# Phototransistor.net
KiCad netlist of a schematic drawn in EAGLE
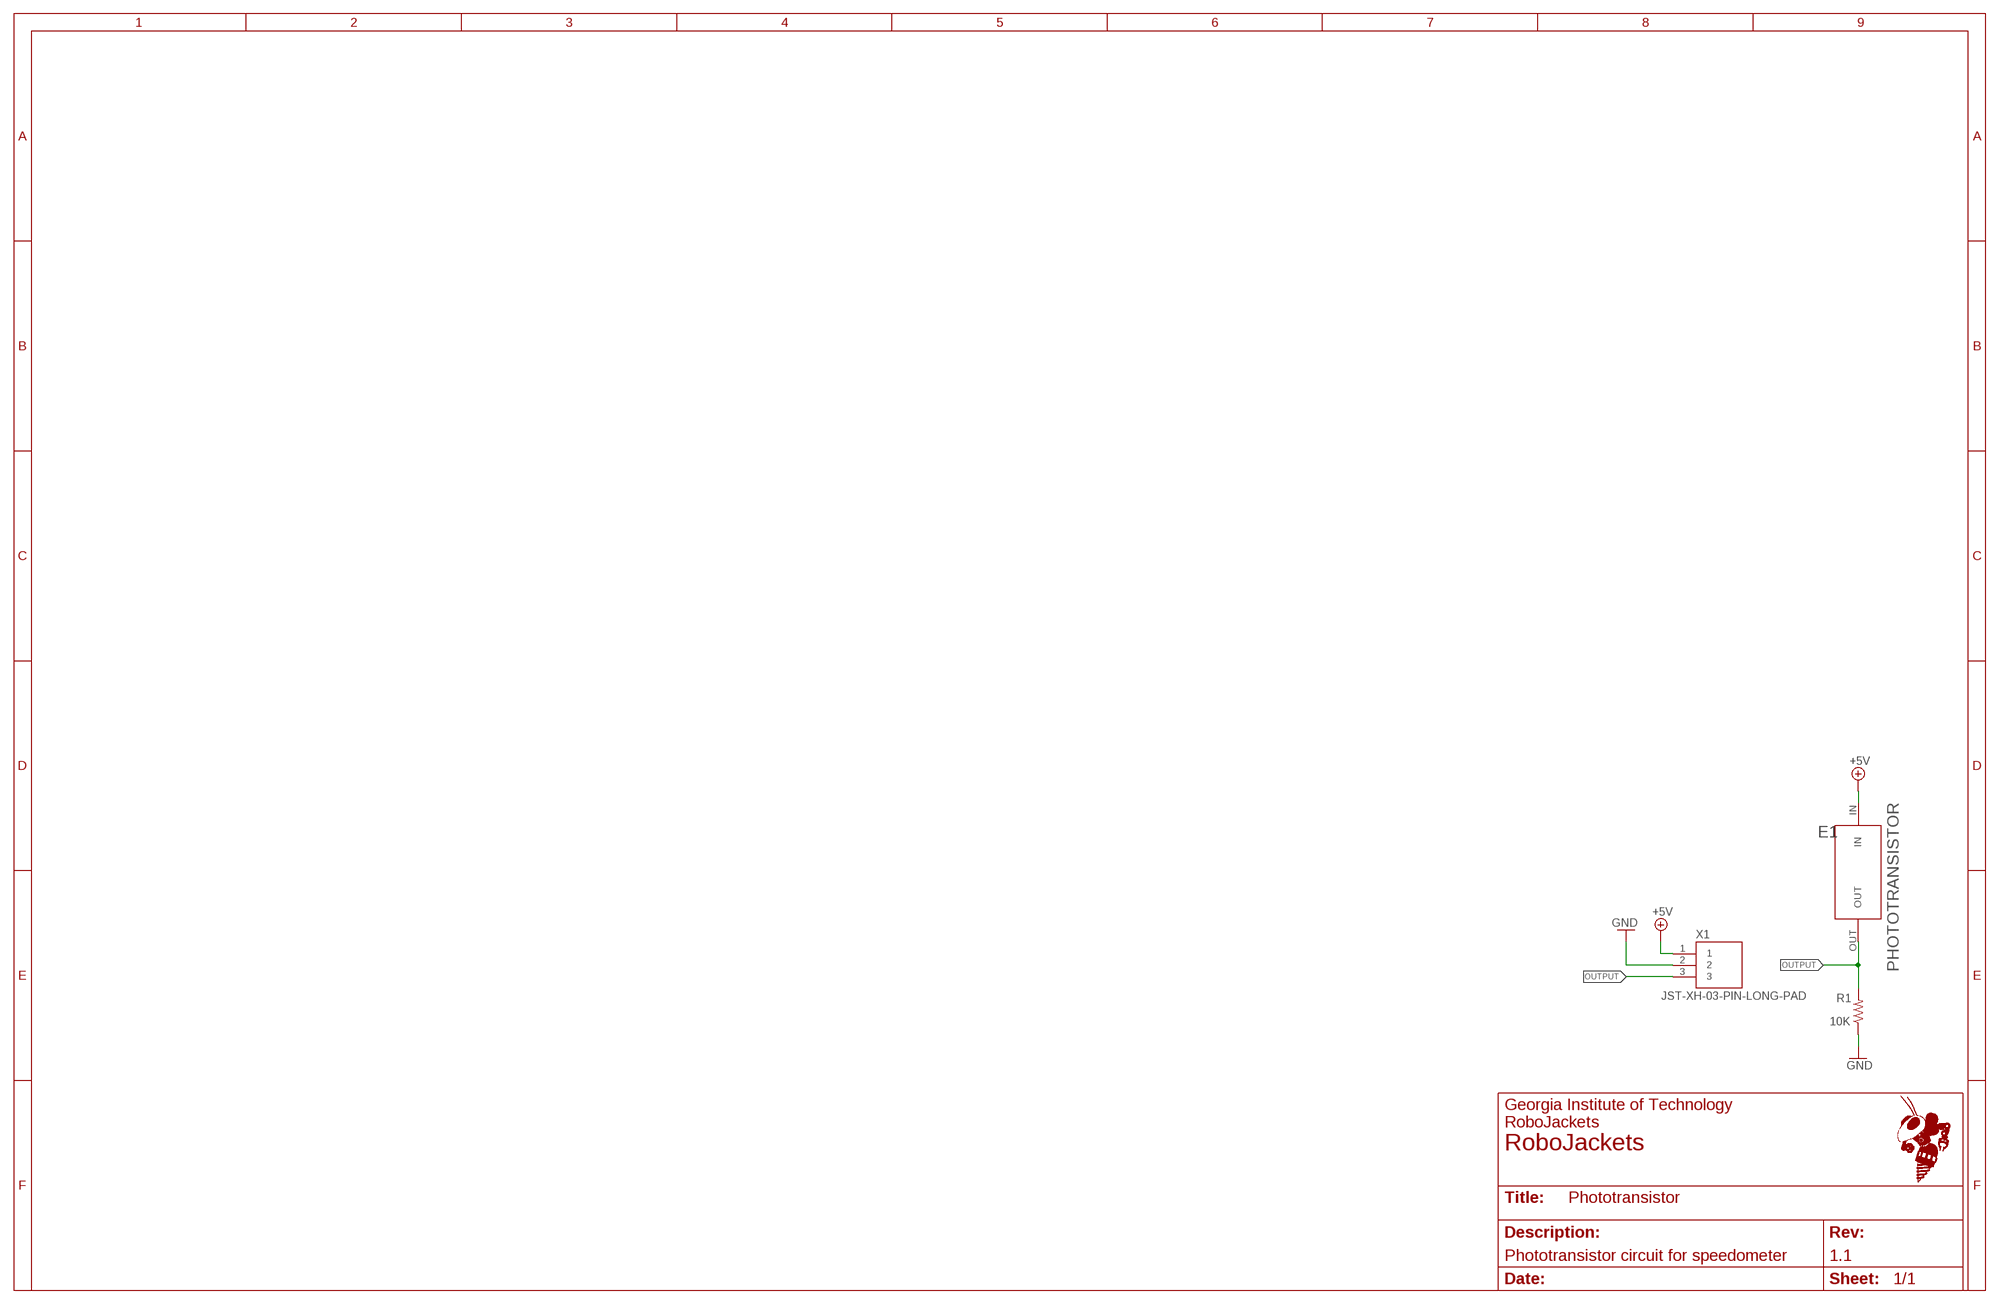
[diagram p0: schematic, sheet 1]

(export (version "E")
  (design (tool "Eeschema 10.0.6"))
  (components
    (comp (ref "E1")
      (value "PHOTOTRANSISTOR")
      (footprint "eagle-import:STD_FP")
      (libsource (lib "eagle-import") (part "PHOTOTRANSISTOR"))
    )
    (comp (ref "R1")
      (value "10K")
      (footprint "eagle-import:R0603")
      (libsource (lib "eagle-import") (part "R-US_R0603"))
    )
    (comp (ref "X1")
      (value "JST-XH-03-PIN-LONG-PAD")
      (footprint "eagle-import:JST-XH-03-PACKAGE-LONG-PAD")
      (libsource (lib "eagle-import") (part "JST-XH-03-PIN-LONG-PAD"))
    )
  )
  (nets
    (net (code "1") (name "+5V") (class "Default")
      (node (ref "E1") (pin "IN") (pinfunction "IN_IN") (pintype "input"))
      (node (ref "X1") (pin "1") (pinfunction "1_1") (pintype "passive"))
    )
    (net (code "2") (name "GND") (class "Default")
      (node (ref "R1") (pin "1") (pinfunction "1_1") (pintype "passive"))
      (node (ref "X1") (pin "2") (pinfunction "2_2") (pintype "passive"))
    )
    (net (code "3") (name "OUTPUT") (class "Default")
      (node (ref "E1") (pin "OUT") (pinfunction "OUT_OUT") (pintype "output"))
      (node (ref "R1") (pin "2") (pinfunction "2_2") (pintype "passive"))
      (node (ref "X1") (pin "3") (pinfunction "3_3") (pintype "passive"))
    )
  )
)
